# BANK0.net
KiCad netlist of a schematic drawn in Altium Designer
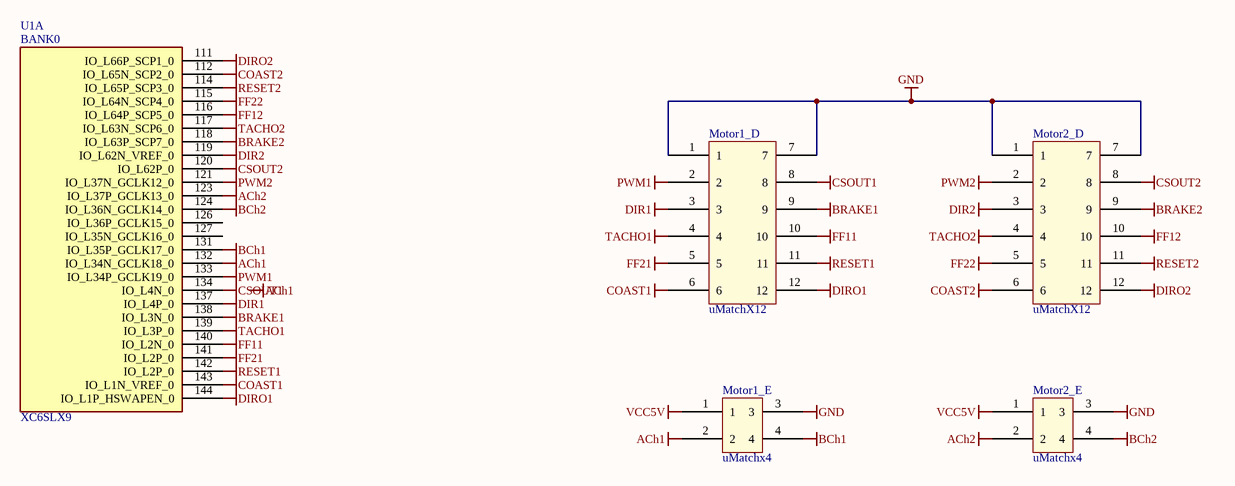
[diagram p0: BANK0.SchDoc]

(export (version "E")
  (design (tool "Eeschema 10.0.6"))
  (components
    (comp (ref "Motor1_D")
      (value "uMatchX12")
      (footprint "uMatchX12")
      (libsource (lib "Mainboard_component_schematics") (part "uMatchX12"))
    )
    (comp (ref "Motor1_E")
      (value "uMatchx4")
      (footprint "Micromatch x4")
      (libsource (lib "Mainboard_component_schematics") (part "uMatchx4"))
    )
    (comp (ref "Motor2_D")
      (value "uMatchX12")
      (footprint "uMatchX12")
      (libsource (lib "Mainboard_component_schematics") (part "uMatchX12"))
    )
    (comp (ref "Motor2_E")
      (value "uMatchx4")
      (footprint "Micromatch x4")
      (libsource (lib "Mainboard_component_schematics") (part "uMatchx4"))
    )
    (comp (ref "U1")
      (value "XC6SLX9")
      (footprint "XC6SLX9")
      (description "Imported")
      (libsource (lib "Mainboard_component_schematics") (part "C6SLX9"))
    )
  )
  (nets
    (net (code "1") (name "ACh1") (class "Default")
      (node (ref "Motor1_E") (pin "2") (pinfunction "2_2") (pintype "passive"))
      (node (ref "U1") (pin "132") (pinfunction "IO_L34N_GCLK18_0_132") (pintype "passive"))
    )
    (net (code "2") (name "ACh2") (class "Default")
      (node (ref "Motor2_E") (pin "2") (pinfunction "2_2") (pintype "passive"))
      (node (ref "U1") (pin "123") (pinfunction "IO_L37P_GCLK13_0_123") (pintype "passive"))
    )
    (net (code "3") (name "BCh1") (class "Default")
      (node (ref "Motor1_E") (pin "4") (pinfunction "4_4") (pintype "passive"))
      (node (ref "U1") (pin "131") (pinfunction "IO_L35P_GCLK17_0_131") (pintype "passive"))
    )
    (net (code "4") (name "BCh2") (class "Default")
      (node (ref "Motor2_E") (pin "4") (pinfunction "4_4") (pintype "passive"))
      (node (ref "U1") (pin "124") (pinfunction "IO_L36N_GCLK14_0_124") (pintype "passive"))
    )
    (net (code "5") (name "BRAKE1") (class "Default")
      (node (ref "Motor1_D") (pin "9") (pinfunction "9_9") (pintype "passive"))
      (node (ref "U1") (pin "138") (pinfunction "IO_L3N_0_138") (pintype "passive"))
    )
    (net (code "6") (name "BRAKE2") (class "Default")
      (node (ref "Motor2_D") (pin "9") (pinfunction "9_9") (pintype "passive"))
      (node (ref "U1") (pin "118") (pinfunction "IO_L63P_SCP7_0_118") (pintype "passive"))
    )
    (net (code "7") (name "COAST1") (class "Default")
      (node (ref "Motor1_D") (pin "6") (pinfunction "6_6") (pintype "passive"))
      (node (ref "U1") (pin "143") (pinfunction "IO_L1N_VREF_0_143") (pintype "passive"))
    )
    (net (code "8") (name "COAST2") (class "Default")
      (node (ref "Motor2_D") (pin "6") (pinfunction "6_6") (pintype "passive"))
      (node (ref "U1") (pin "112") (pinfunction "IO_L65N_SCP2_0_112") (pintype "passive"))
    )
    (net (code "9") (name "CSOUT1") (class "Default")
      (node (ref "Motor1_D") (pin "8") (pinfunction "8_8") (pintype "passive"))
      (node (ref "U1") (pin "134") (pinfunction "IO_L4N_0_134") (pintype "passive"))
    )
    (net (code "10") (name "CSOUT2") (class "Default")
      (node (ref "Motor2_D") (pin "8") (pinfunction "8_8") (pintype "passive"))
      (node (ref "U1") (pin "120") (pinfunction "IO_L62P_0_120") (pintype "passive"))
    )
    (net (code "11") (name "DIR1") (class "Default")
      (node (ref "Motor1_D") (pin "3") (pinfunction "3_3") (pintype "passive"))
      (node (ref "U1") (pin "137") (pinfunction "IO_L4P_0_137") (pintype "passive"))
    )
    (net (code "12") (name "DIR2") (class "Default")
      (node (ref "Motor2_D") (pin "3") (pinfunction "3_3") (pintype "passive"))
      (node (ref "U1") (pin "119") (pinfunction "IO_L62N_VREF_0_119") (pintype "passive"))
    )
    (net (code "13") (name "DIRO1") (class "Default")
      (node (ref "Motor1_D") (pin "12") (pinfunction "12_12") (pintype "passive"))
      (node (ref "U1") (pin "144") (pinfunction "IO_L1P_HSWAPEN_0_144") (pintype "passive"))
    )
    (net (code "14") (name "DIRO2") (class "Default")
      (node (ref "Motor2_D") (pin "12") (pinfunction "12_12") (pintype "passive"))
      (node (ref "U1") (pin "111") (pinfunction "IO_L66P_SCP1_0_111") (pintype "passive"))
    )
    (net (code "15") (name "FF11") (class "Default")
      (node (ref "Motor1_D") (pin "10") (pinfunction "10_10") (pintype "passive"))
      (node (ref "U1") (pin "140") (pinfunction "IO_L2N_0_140") (pintype "passive"))
    )
    (net (code "16") (name "FF12") (class "Default")
      (node (ref "Motor2_D") (pin "10") (pinfunction "10_10") (pintype "passive"))
      (node (ref "U1") (pin "116") (pinfunction "IO_L64P_SCP5_0_116") (pintype "passive"))
    )
    (net (code "17") (name "FF21") (class "Default")
      (node (ref "Motor1_D") (pin "5") (pinfunction "5_5") (pintype "passive"))
      (node (ref "U1") (pin "141") (pinfunction "IO_L2P_0_141") (pintype "passive"))
    )
    (net (code "18") (name "FF22") (class "Default")
      (node (ref "Motor2_D") (pin "5") (pinfunction "5_5") (pintype "passive"))
      (node (ref "U1") (pin "115") (pinfunction "IO_L64N_SCP4_0_115") (pintype "passive"))
    )
    (net (code "19") (name "GND") (class "Default")
      (node (ref "Motor1_D") (pin "1") (pinfunction "1_1") (pintype "passive"))
      (node (ref "Motor1_D") (pin "7") (pinfunction "7_7") (pintype "passive"))
      (node (ref "Motor1_E") (pin "3") (pinfunction "3_3") (pintype "passive"))
      (node (ref "Motor2_D") (pin "1") (pinfunction "1_1") (pintype "passive"))
      (node (ref "Motor2_D") (pin "7") (pinfunction "7_7") (pintype "passive"))
      (node (ref "Motor2_E") (pin "3") (pinfunction "3_3") (pintype "passive"))
    )
    (net (code "20") (name "PWM1") (class "Default")
      (node (ref "Motor1_D") (pin "2") (pinfunction "2_2") (pintype "passive"))
      (node (ref "U1") (pin "133") (pinfunction "IO_L34P_GCLK19_0_133") (pintype "passive"))
    )
    (net (code "21") (name "PWM2") (class "Default")
      (node (ref "Motor2_D") (pin "2") (pinfunction "2_2") (pintype "passive"))
      (node (ref "U1") (pin "121") (pinfunction "IO_L37N_GCLK12_0_121") (pintype "passive"))
    )
    (net (code "22") (name "RESET1") (class "Default")
      (node (ref "Motor1_D") (pin "11") (pinfunction "11_11") (pintype "passive"))
      (node (ref "U1") (pin "142") (pinfunction "IO_L2P_0_142") (pintype "passive"))
    )
    (net (code "23") (name "RESET2") (class "Default")
      (node (ref "Motor2_D") (pin "11") (pinfunction "11_11") (pintype "passive"))
      (node (ref "U1") (pin "114") (pinfunction "IO_L65P_SCP3_0_114") (pintype "passive"))
    )
    (net (code "24") (name "TACHO1") (class "Default")
      (node (ref "Motor1_D") (pin "4") (pinfunction "4_4") (pintype "passive"))
      (node (ref "U1") (pin "139") (pinfunction "IO_L3P_0_139") (pintype "passive"))
    )
    (net (code "25") (name "TACHO2") (class "Default")
      (node (ref "Motor2_D") (pin "4") (pinfunction "4_4") (pintype "passive"))
      (node (ref "U1") (pin "117") (pinfunction "IO_L63N_SCP6_0_117") (pintype "passive"))
    )
    (net (code "26") (name "VCC5V") (class "Default")
      (node (ref "Motor1_E") (pin "1") (pinfunction "1_1") (pintype "passive"))
      (node (ref "Motor2_E") (pin "1") (pinfunction "1_1") (pintype "passive"))
    )
    (net (code "27") (name "unconnected-(U1A-IO_L35N_GCLK16_0-Pad127)") (class "Default")
      (node (ref "U1") (pin "127") (pinfunction "IO_L35N_GCLK16_0_127") (pintype "passive"))
    )
    (net (code "28") (name "unconnected-(U1A-IO_L36P_GCLK15_0-Pad126)") (class "Default")
      (node (ref "U1") (pin "126") (pinfunction "IO_L36P_GCLK15_0_126") (pintype "passive"))
    )
  )
)
